# CAN_SCH.net
KiCad netlist of a schematic drawn in Altium Designer
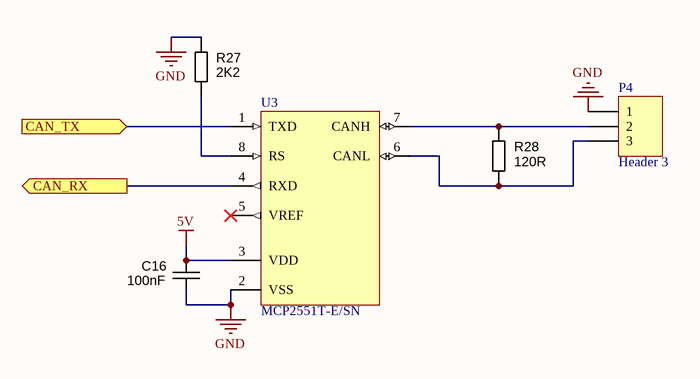
[diagram p0: CAN_SCH.SchDoc]

(export (version "E")
  (design (tool "Eeschema 10.0.6"))
  (components
    (comp (ref "C16")
      (value "100nF")
      (footprint "CAPC1608X90N")
      (description "Capacitor SMD Cer 100nF 10% 50V X7R 0603")
      (fields (field (name "TOLERANCE") "±10%"))
      (libsource (lib "PBL - Capacitors") (part "CAPC_47n_0603_X7R_50V_10%"))
    )
    (comp (ref "P4")
      (value "Header 3")
      (footprint "HDR1X3")
      (description "Header, 3-Pin")
      (fields (field (name "PUBLISHER") "Altium Limited"))
      (libsource (lib "Miscellaneous Connectors") (part "Header 3"))
    )
    (comp (ref "R27")
      (value "2K2")
      (footprint "RESC1608N_ZERO")
      (description "Resistor SMD 0603 2.2K 5%")
      (fields (field (name "TOLERANCE") "±5%"))
      (libsource (lib "PBL - Resistors") (part "RES_0R_0603"))
    )
    (comp (ref "R28")
      (value "120R")
      (footprint "RESC1608N_ZERO")
      (description "Resistor SMD 0603 120 Ohm 5%")
      (fields (field (name "TOLERANCE") "±5%"))
      (libsource (lib "PBL - Resistors") (part "RES_0R_0603"))
    )
    (comp (ref "U3")
      (value "MCP2551T-E/SN")
      (footprint "SOIC-SN8_M")
      (description "High-Speed CAN Transceiver, 8-Pin SOIC, Extended Temperature, Tape and Reel")
      (libsource (lib "Altium Content Vault") (part "COM-TRX-MCP2551-8"))
    )
  )
  (nets
    (net (code "1") (name "/CAN_RX") (class "Default")
      (node (ref "U3") (pin "4") (pinfunction "RXD_4") (pintype "output"))
    )
    (net (code "2") (name "/CAN_TX") (class "Default")
      (node (ref "U3") (pin "1") (pinfunction "TXD_1") (pintype "input"))
    )
    (net (code "3") (name "5V") (class "Default")
      (node (ref "C16") (pin "1") (pintype "passive"))
      (node (ref "U3") (pin "3") (pinfunction "VDD_3") (pintype "power_in"))
    )
    (net (code "4") (name "GND") (class "Default")
      (node (ref "C16") (pin "2") (pintype "passive"))
      (node (ref "P4") (pin "1") (pinfunction "1_1") (pintype "passive"))
      (node (ref "R27") (pin "1") (pinfunction "1_1") (pintype "passive"))
      (node (ref "U3") (pin "2") (pinfunction "VSS_2") (pintype "power_in"))
    )
    (net (code "5") (name "Net-(U3-CANH)") (class "Default")
      (node (ref "P4") (pin "2") (pinfunction "2_2") (pintype "passive"))
      (node (ref "R28") (pin "1") (pinfunction "1_1") (pintype "passive"))
      (node (ref "U3") (pin "7") (pinfunction "CANH_7") (pintype "bidirectional"))
    )
    (net (code "6") (name "Net-(U3-CANL)") (class "Default")
      (node (ref "P4") (pin "3") (pinfunction "3_3") (pintype "passive"))
      (node (ref "R28") (pin "2") (pinfunction "2_2") (pintype "passive"))
      (node (ref "U3") (pin "6") (pinfunction "CANL_6") (pintype "bidirectional"))
    )
    (net (code "7") (name "Net-(U3-RS)") (class "Default")
      (node (ref "R27") (pin "2") (pinfunction "2_2") (pintype "passive"))
      (node (ref "U3") (pin "8") (pinfunction "RS_8") (pintype "input"))
    )
    (net (code "8") (name "unconnected-(U3-VREF-Pad5)") (class "Default")
      (node (ref "U3") (pin "5") (pinfunction "VREF_5") (pintype "output+no_connect"))
    )
  )
)
